# Main.net
KiCad netlist of a schematic drawn in Altium Designer
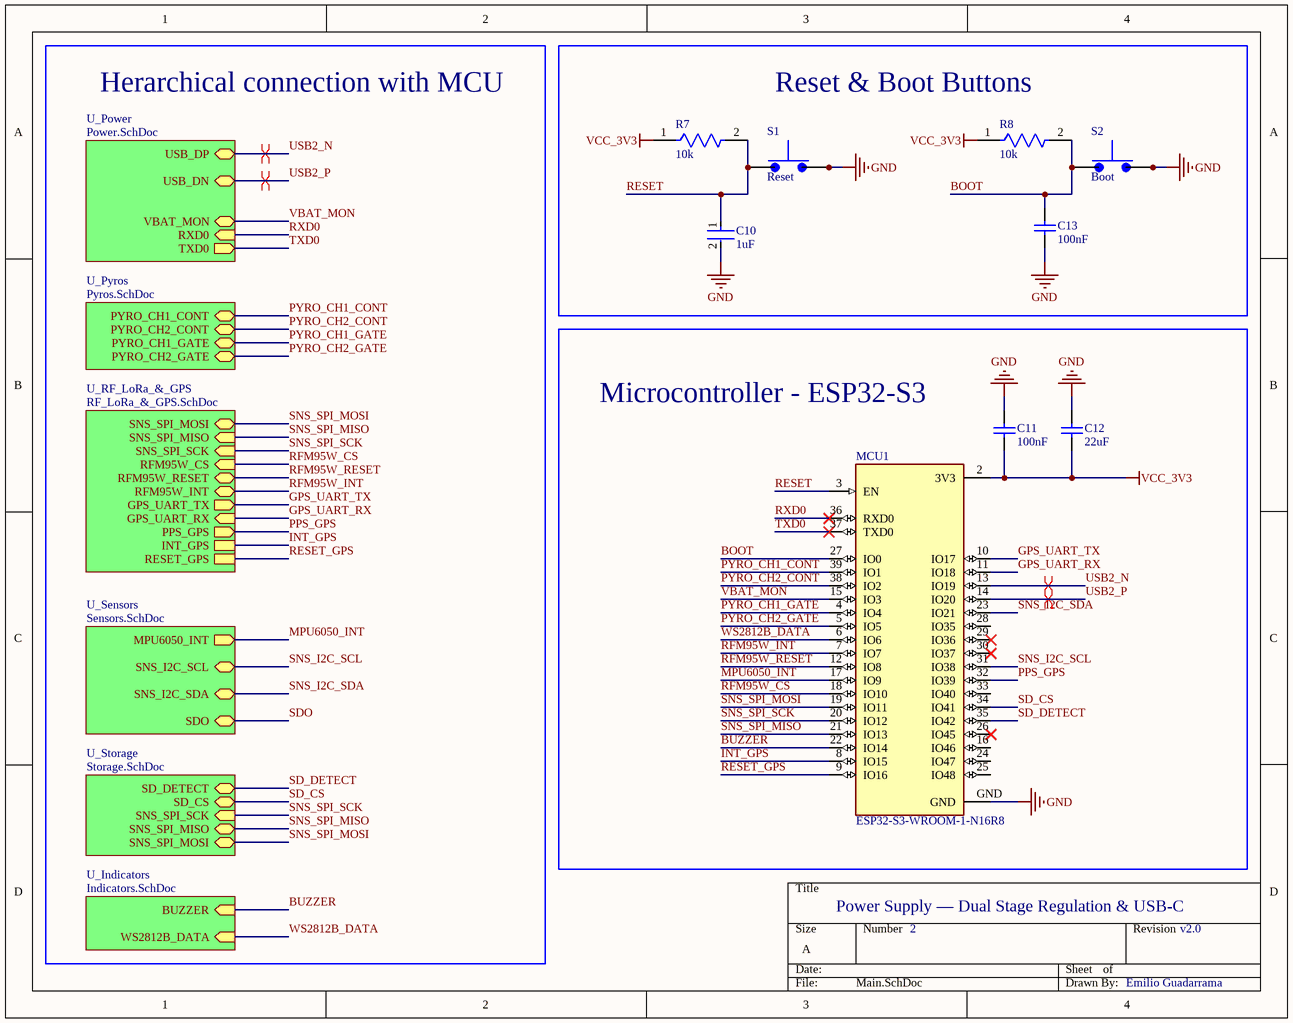
[diagram p0: Main.SchDoc]

(export (version "E")
  (design (tool "Eeschema 10.0.6"))
  (components
    (comp (ref "C10")
      (value "1uF")
      (footprint "FP-0805-L_2_01_0_2-W_1_25-MFG")
      (description "08051C105K4T2A Cap Ceramic 1uF 100V X7R 10% Pad SMD 0805 125C Automotive T/R")
      (fields (field (name "TOLERANCE") "10%"))
      (libsource (lib "Altium Content Vault") (part "b4654b650e69147ec39a6b967a45e02"))
    )
    (comp (ref "C11")
      (value "100nF")
      (footprint "CAPC2013X145X50NL20T25")
      (fields (field (name "MANUFACTURER") "Kemet") (field (name "PART NUMBER") "C0805S104K5RACTU"))
      (libsource (lib "Altium Content Vault") (part "CAP"))
    )
    (comp (ref "C12")
      (value "22uF")
      (footprint "CAPC0805(2012)145_L")
      (description "CAP 22uF 6.3V ±10% 0805 (2012 Metric) Thickness 1.45mm SMD")
      (fields (field (name "TOLERANCE") "Â±10%"))
      (libsource (lib "Altium Content Vault") (part "CAP"))
    )
    (comp (ref "C13")
      (value "100nF")
      (footprint "CAPC2013X145X50NL20T25")
      (fields (field (name "MANUFACTURER") "Kemet") (field (name "PART NUMBER") "C0805S104K5RACTU"))
      (libsource (lib "Altium Content Vault") (part "CAP"))
    )
    (comp (ref "MCU1")
      (value "ESP32-S3-WROOM-1-N16R8")
      (footprint "XCVR_ESP32-S3-WROOM-1-N16R2")
      (description "Bluetooth, WiFi 802.11b/g/n, Bluetooth v5.0 Transceiver Module 2.4GHz PCB Trace Surface Mount")
      (fields (field (name "MF") "Espressif Systems") (field (name "MP") "ESP32S3WROOM1N16R2"))
      (libsource (lib "ESP32-S3-WROOM-1-N16R2") (part "ESP32-S3-WROOM-1-N16R2"))
    )
    (comp (ref "R7")
      (value "10k")
      (footprint "FP-MCT0603-IPC_A")
      (description "RES SMD 100 OHM 1% 1/8W 0603")
      (fields (field (name "TOLERANCE") "0.1%"))
      (libsource (lib "Altium Content Vault") (part "1029c3af85768c4190bb7ad29bc67b5"))
    )
    (comp (ref "R8")
      (value "10k")
      (footprint "FP-MCT0603-IPC_A")
      (description "RES SMD 100 OHM 1% 1/8W 0603")
      (fields (field (name "TOLERANCE") "0.1%"))
      (libsource (lib "Altium Content Vault") (part "1029c3af85768c4190bb7ad29bc67b5"))
    )
    (comp (ref "S1")
      (value "Reset")
      (footprint "SW_SKRPABE010")
      (description "Switch Tactile N.O. SPST Button J-Bend 0.05A 16VDC 1.57N SMD Automotive T/R")
      (fields (field (name "MF") "ALPS") (field (name "MP") "SKRPABE010"))
      (libsource (lib "Button-SKRPABE010") (part "SKRPABE010"))
    )
    (comp (ref "S2")
      (value "Boot")
      (footprint "SW_SKRPABE010")
      (description "Switch Tactile N.O. SPST Button J-Bend 0.05A 16VDC 1.57N SMD Automotive T/R")
      (fields (field (name "MF") "ALPS") (field (name "MP") "SKRPABE010"))
      (libsource (lib "Button-SKRPABE010") (part "SKRPABE010"))
    )
  )
  (nets
    (net (code "2") (name "/BOOT") (class "Default")
      (node (ref "C13") (pin "2") (pinfunction "2_2") (pintype "passive"))
      (node (ref "MCU1") (pin "27") (pinfunction "IO0_27") (pintype "bidirectional"))
      (node (ref "R8") (pin "2") (pinfunction "2_2") (pintype "passive"))
      (node (ref "S2") (pin "1") (pinfunction "1_1") (pintype "passive"))
      (node (ref "S2") (pin "2") (pinfunction "1_2") (pintype "passive"))
    )
    (net (code "3") (name "/BUZZER") (class "Default")
      (node (ref "MCU1") (pin "22") (pinfunction "IO14_22") (pintype "bidirectional"))
    )
    (net (code "4") (name "/GPS_UART_RX") (class "Default")
      (node (ref "MCU1") (pin "11") (pinfunction "IO18_11") (pintype "bidirectional"))
    )
    (net (code "5") (name "/GPS_UART_TX") (class "Default")
      (node (ref "MCU1") (pin "10") (pinfunction "IO17_10") (pintype "bidirectional"))
    )
    (net (code "6") (name "/INT_GPS") (class "Default")
      (node (ref "MCU1") (pin "8") (pinfunction "IO15_8") (pintype "bidirectional"))
    )
    (net (code "7") (name "/MPU6050_INT") (class "Default")
      (node (ref "MCU1") (pin "17") (pinfunction "IO9_17") (pintype "bidirectional"))
    )
    (net (code "8") (name "/PPS_GPS") (class "Default")
      (node (ref "MCU1") (pin "32") (pinfunction "IO39_32") (pintype "bidirectional"))
    )
    (net (code "9") (name "/PYRO_CH1_CONT") (class "Default")
      (node (ref "MCU1") (pin "39") (pinfunction "IO1_39") (pintype "bidirectional"))
    )
    (net (code "10") (name "/PYRO_CH1_GATE") (class "Default")
      (node (ref "MCU1") (pin "4") (pinfunction "IO4_4") (pintype "bidirectional"))
    )
    (net (code "11") (name "/PYRO_CH2_CONT") (class "Default")
      (node (ref "MCU1") (pin "38") (pinfunction "IO2_38") (pintype "bidirectional"))
    )
    (net (code "12") (name "/PYRO_CH2_GATE") (class "Default")
      (node (ref "MCU1") (pin "5") (pinfunction "IO5_5") (pintype "bidirectional"))
    )
    (net (code "13") (name "/RESET") (class "Default")
      (node (ref "C10") (pin "1") (pinfunction "1_1") (pintype "passive"))
      (node (ref "MCU1") (pin "3") (pinfunction "EN_3") (pintype "input"))
      (node (ref "R7") (pin "2") (pinfunction "2_2") (pintype "passive"))
      (node (ref "S1") (pin "1") (pinfunction "1_1") (pintype "passive"))
      (node (ref "S1") (pin "2") (pinfunction "1_2") (pintype "passive"))
    )
    (net (code "14") (name "/RESET_GPS") (class "Default")
      (node (ref "MCU1") (pin "9") (pinfunction "IO16_9") (pintype "bidirectional"))
    )
    (net (code "15") (name "/RFM95W_CS") (class "Default")
      (node (ref "MCU1") (pin "18") (pinfunction "IO10_18") (pintype "bidirectional"))
    )
    (net (code "16") (name "/RFM95W_INT") (class "Default")
      (node (ref "MCU1") (pin "7") (pinfunction "IO7_7") (pintype "bidirectional"))
    )
    (net (code "17") (name "/RFM95W_RESET") (class "Default")
      (node (ref "MCU1") (pin "12") (pinfunction "IO8_12") (pintype "bidirectional"))
    )
    (net (code "18") (name "/RXD0") (class "Default")
      (node (ref "MCU1") (pin "36") (pinfunction "RXD0_36") (pintype "bidirectional+no_connect"))
    )
    (net (code "20") (name "/SD_CS") (class "Default")
      (node (ref "MCU1") (pin "34") (pinfunction "IO41_34") (pintype "bidirectional"))
    )
    (net (code "21") (name "/SD_DETECT") (class "Default")
      (node (ref "MCU1") (pin "35") (pinfunction "IO42_35") (pintype "bidirectional"))
    )
    (net (code "22") (name "/SNS_I2C_SCL") (class "Default")
      (node (ref "MCU1") (pin "31") (pinfunction "IO38_31") (pintype "bidirectional"))
    )
    (net (code "23") (name "/SNS_I2C_SDA") (class "Default")
      (node (ref "MCU1") (pin "23") (pinfunction "IO21_23") (pintype "bidirectional"))
    )
    (net (code "24") (name "/SNS_SPI_MISO") (class "Default")
      (node (ref "MCU1") (pin "21") (pinfunction "IO13_21") (pintype "bidirectional"))
    )
    (net (code "25") (name "/SNS_SPI_MOSI") (class "Default")
      (node (ref "MCU1") (pin "19") (pinfunction "IO11_19") (pintype "bidirectional"))
    )
    (net (code "26") (name "/SNS_SPI_SCK") (class "Default")
      (node (ref "MCU1") (pin "20") (pinfunction "IO12_20") (pintype "bidirectional"))
    )
    (net (code "27") (name "/TXD0") (class "Default")
      (node (ref "MCU1") (pin "37") (pinfunction "TXD0_37") (pintype "bidirectional"))
    )
    (net (code "28") (name "/USB2_N") (class "Default")
      (node (ref "MCU1") (pin "13") (pinfunction "IO19_13") (pintype "bidirectional"))
    )
    (net (code "29") (name "/USB2_P") (class "Default")
      (node (ref "MCU1") (pin "14") (pinfunction "IO20_14") (pintype "bidirectional"))
    )
    (net (code "30") (name "/VBAT_MON") (class "Default")
      (node (ref "MCU1") (pin "15") (pinfunction "IO3_15") (pintype "bidirectional"))
    )
    (net (code "31") (name "/WS2812B_DATA") (class "Default")
      (node (ref "MCU1") (pin "6") (pinfunction "IO6_6") (pintype "bidirectional"))
    )
    (net (code "32") (name "GND") (class "Default")
      (node (ref "C10") (pin "2") (pinfunction "2_2") (pintype "passive"))
      (node (ref "C11") (pin "2") (pinfunction "2_2") (pintype "passive"))
      (node (ref "C12") (pin "2") (pinfunction "2_2") (pintype "passive"))
      (node (ref "C13") (pin "1") (pinfunction "1_1") (pintype "passive"))
      (node (ref "MCU1") (pin "GND") (pinfunction "GND_GND") (pintype "power_in"))
      (node (ref "S1") (pin "3") (pinfunction "2_3") (pintype "passive"))
      (node (ref "S1") (pin "4") (pinfunction "2_4") (pintype "passive"))
      (node (ref "S2") (pin "3") (pinfunction "2_3") (pintype "passive"))
      (node (ref "S2") (pin "4") (pinfunction "2_4") (pintype "passive"))
    )
    (net (code "33") (name "VCC_3V3") (class "Default")
      (node (ref "C11") (pin "1") (pinfunction "1_1") (pintype "passive"))
      (node (ref "C12") (pin "1") (pinfunction "1_1") (pintype "passive"))
      (node (ref "MCU1") (pin "2") (pinfunction "3V3_2") (pintype "power_in"))
      (node (ref "R7") (pin "1") (pinfunction "1_1") (pintype "passive"))
      (node (ref "R8") (pin "1") (pinfunction "1_1") (pintype "passive"))
    )
    (net (code "34") (name "unconnected-(MCU1-IO35-Pad28)") (class "Default")
      (node (ref "MCU1") (pin "28") (pinfunction "IO35_28") (pintype "bidirectional"))
    )
    (net (code "35") (name "unconnected-(MCU1-IO36-Pad29)") (class "Default")
      (node (ref "MCU1") (pin "29") (pinfunction "IO36_29") (pintype "bidirectional+no_connect"))
    )
    (net (code "36") (name "unconnected-(MCU1-IO37-Pad30)") (class "Default")
      (node (ref "MCU1") (pin "30") (pinfunction "IO37_30") (pintype "bidirectional+no_connect"))
    )
    (net (code "37") (name "unconnected-(MCU1-IO40-Pad33)") (class "Default")
      (node (ref "MCU1") (pin "33") (pinfunction "IO40_33") (pintype "bidirectional"))
    )
    (net (code "38") (name "unconnected-(MCU1-IO45-Pad26)") (class "Default")
      (node (ref "MCU1") (pin "26") (pinfunction "IO45_26") (pintype "bidirectional+no_connect"))
    )
    (net (code "39") (name "unconnected-(MCU1-IO46-Pad16)") (class "Default")
      (node (ref "MCU1") (pin "16") (pinfunction "IO46_16") (pintype "bidirectional"))
    )
    (net (code "40") (name "unconnected-(MCU1-IO47-Pad24)") (class "Default")
      (node (ref "MCU1") (pin "24") (pinfunction "IO47_24") (pintype "bidirectional"))
    )
    (net (code "41") (name "unconnected-(MCU1-IO48-Pad25)") (class "Default")
      (node (ref "MCU1") (pin "25") (pinfunction "IO48_25") (pintype "bidirectional"))
    )
  )
)
